# EMS-ESP8266-12.net
KiCad netlist of a schematic drawn in EAGLE
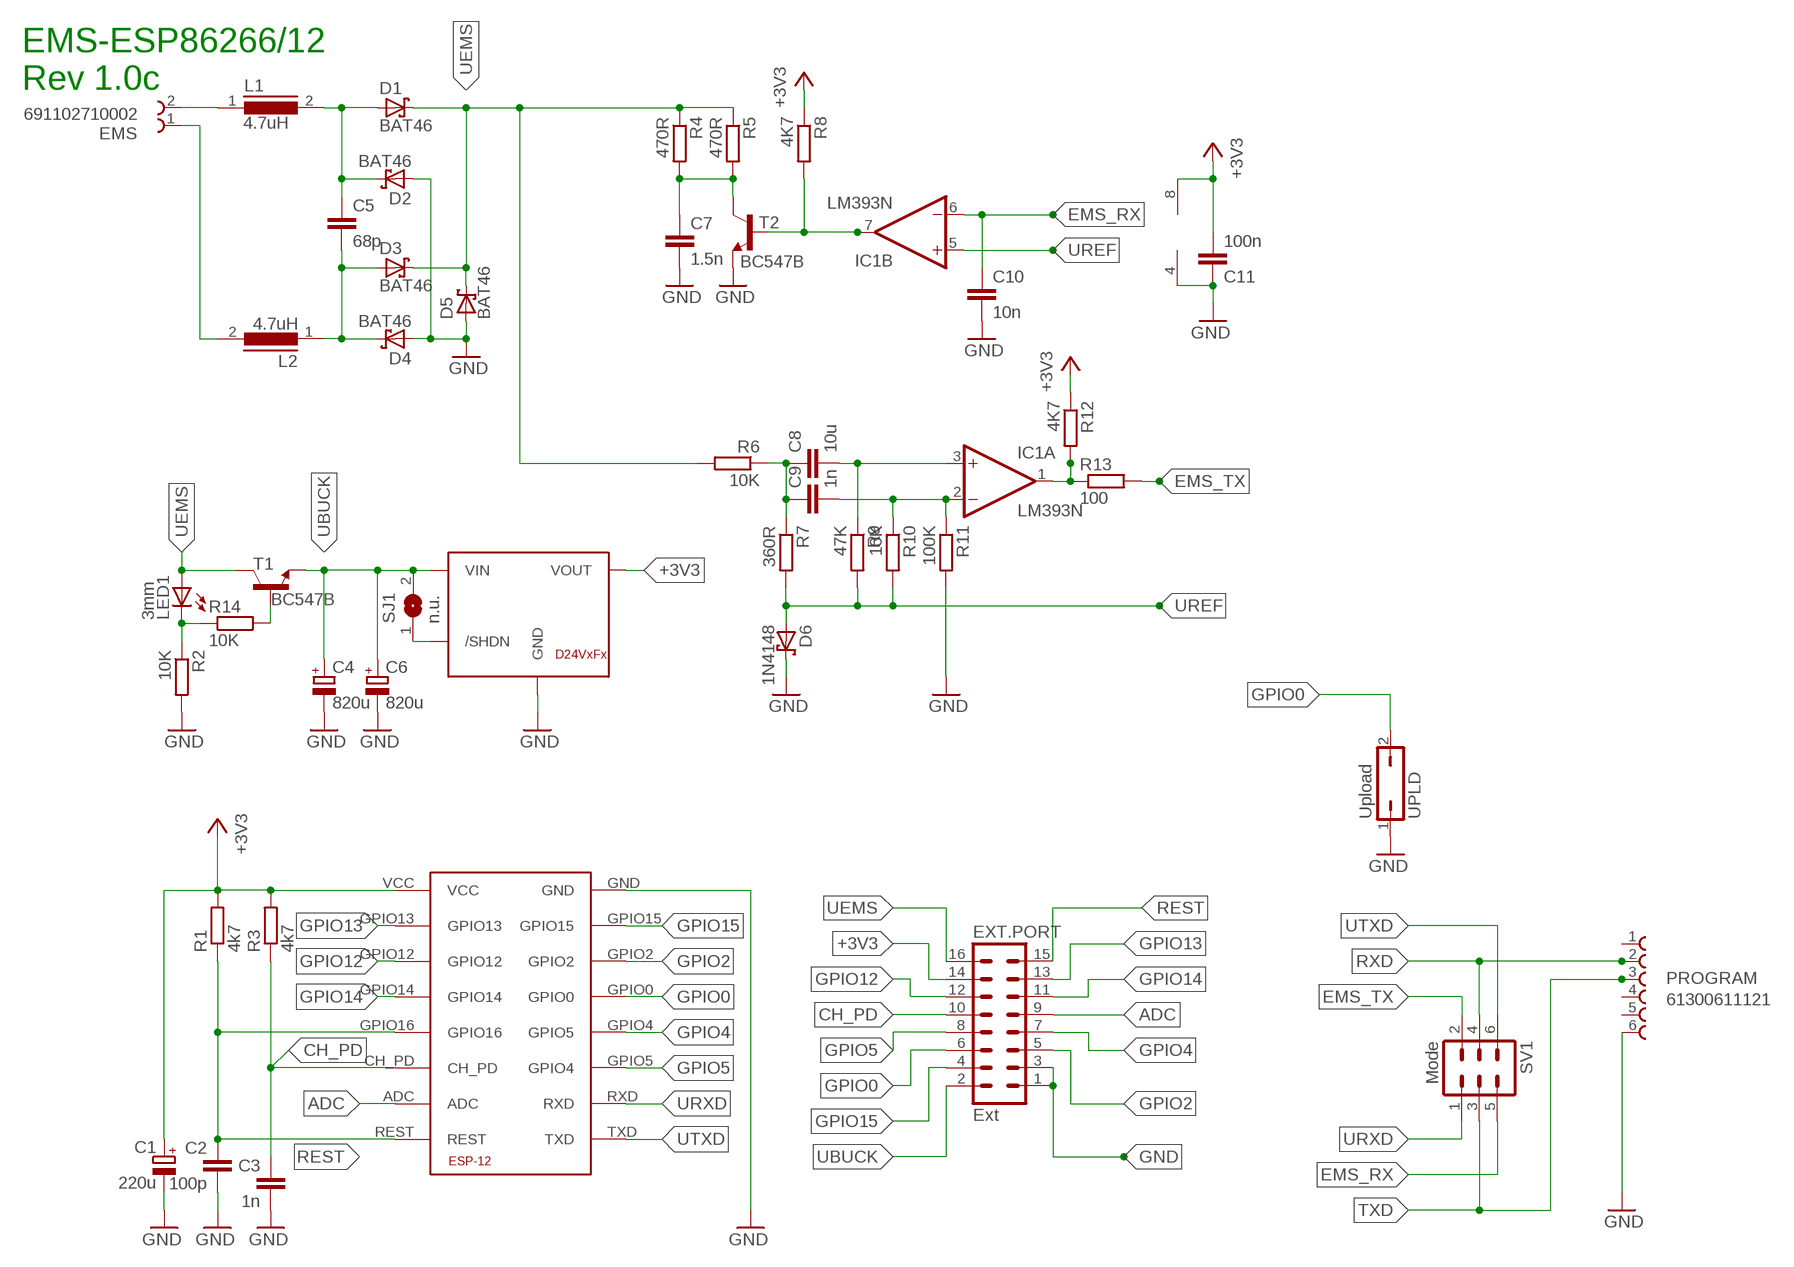
[diagram p0: schematic, sheet 1]

(export (version "E")
  (design (tool "Eeschema 10.0.6"))
  (components
    (comp (ref "C1")
      (value "220u")
      (footprint "eagle-import:UD-6,3X5,8_NICHICON")
      (libsource (lib "eagle-import") (part "CPOL-EUUD-6,3X8,8"))
    )
    (comp (ref "C2")
      (value "100p")
      (footprint "eagle-import:C2.5-2")
      (libsource (lib "eagle-import") (part "C2.5/2"))
    )
    (comp (ref "C3")
      (value "1n")
      (footprint "eagle-import:C2.5-2")
      (libsource (lib "eagle-import") (part "C2.5/2"))
    )
    (comp (ref "C4")
      (value "820u")
      (footprint "eagle-import:UD-10X10_NICHICON")
      (libsource (lib "eagle-import") (part "CPOL-EUUD-10X10"))
    )
    (comp (ref "C5")
      (value "68p")
      (footprint "eagle-import:C025-050X050")
      (libsource (lib "eagle-import") (part "C-EU025-050X050"))
    )
    (comp (ref "C6")
      (value "820u")
      (footprint "eagle-import:UD-10X10_NICHICON")
      (libsource (lib "eagle-import") (part "CPOL-EUUD-10X10"))
    )
    (comp (ref "C7")
      (value "1.5n")
      (footprint "eagle-import:C2.5-2")
      (libsource (lib "eagle-import") (part "C2.5/2"))
    )
    (comp (ref "C8")
      (value "10u")
      (footprint "eagle-import:C5B11")
      (libsource (lib "eagle-import") (part "C5/11"))
    )
    (comp (ref "C9")
      (value "1n")
      (footprint "eagle-import:C2.5-2")
      (libsource (lib "eagle-import") (part "C2.5/2"))
    )
    (comp (ref "C10")
      (value "10n")
      (footprint "eagle-import:C2.5-2")
      (libsource (lib "eagle-import") (part "C2.5/2"))
    )
    (comp (ref "C11")
      (value "100n")
      (footprint "eagle-import:C2.5-2")
      (libsource (lib "eagle-import") (part "C2.5/2"))
    )
    (comp (ref "D1")
      (value "BAT46")
      (footprint "eagle-import:DO35-7")
      (libsource (lib "eagle-import") (part "SCHOTTKY-DIODEDO35-7"))
    )
    (comp (ref "D2")
      (value "BAT46")
      (footprint "eagle-import:DO35-7")
      (libsource (lib "eagle-import") (part "SCHOTTKY-DIODEDO35-7"))
    )
    (comp (ref "D3")
      (value "BAT46")
      (footprint "eagle-import:DO35-7")
      (libsource (lib "eagle-import") (part "SCHOTTKY-DIODEDO35-7"))
    )
    (comp (ref "D4")
      (value "BAT46")
      (footprint "eagle-import:DO35-7")
      (libsource (lib "eagle-import") (part "SCHOTTKY-DIODEDO35-7"))
    )
    (comp (ref "D5")
      (value "BAT46")
      (footprint "eagle-import:DO35-7")
      (libsource (lib "eagle-import") (part "SCHOTTKY-DIODEDO35-7"))
    )
    (comp (ref "D6")
      (value "1N4148")
      (footprint "eagle-import:DO35-7")
      (libsource (lib "eagle-import") (part "SCHOTTKY-DIODEDO35-7"))
    )
    (comp (ref "EMS")
      (value "691102710002")
      (footprint "eagle-import:691102710002")
      (libsource (lib "eagle-import") (part "691102710002"))
    )
    (comp (ref "ESP1")
      (value "ESP-12ESP-12")
      (footprint "eagle-import:ESP-12")
      (libsource (lib "eagle-import") (part "ESP-12ESP-12"))
    )
    (comp (ref "EXT.PORT")
      (value "Ext")
      (footprint "eagle-import:MA08-2")
      (libsource (lib "eagle-import") (part "MA08-2"))
    )
    (comp (ref "IC1")
      (value "LM393N")
      (footprint "eagle-import:DIL08")
      (fields (field (name "REICHELT") "LM 393 DIP"))
      (libsource (lib "eagle-import") (part "LM393N"))
    )
    (comp (ref "L1")
      (value "4.7uH")
      (footprint "eagle-import:MICC12")
      (libsource (lib "eagle-import") (part "MICC12"))
    )
    (comp (ref "L2")
      (value "4.7uH")
      (footprint "eagle-import:MICC12")
      (libsource (lib "eagle-import") (part "MICC12"))
    )
    (comp (ref "LED1")
      (value "3mm")
      (footprint "eagle-import:LED3MM")
      (libsource (lib "eagle-import") (part "LED3MM"))
    )
    (comp (ref "MOD1")
      (value "D24V3F3")
      (footprint "eagle-import:D24VXFX")
      (libsource (lib "eagle-import") (part "D24VXFX"))
    )
    (comp (ref "PROGRAM")
      (value "61300611121")
      (footprint "eagle-import:61300611121")
      (libsource (lib "eagle-import") (part "61300611121"))
    )
    (comp (ref "R1")
      (value "4k7")
      (footprint "eagle-import:0204_7")
      (libsource (lib "eagle-import") (part "R-EU_0204/7"))
    )
    (comp (ref "R2")
      (value "10K")
      (footprint "eagle-import:0204_7")
      (libsource (lib "eagle-import") (part "R-EU_0204/7"))
    )
    (comp (ref "R3")
      (value "4k7")
      (footprint "eagle-import:0204_7")
      (libsource (lib "eagle-import") (part "R-EU_0204/7"))
    )
    (comp (ref "R4")
      (value "470R")
      (footprint "eagle-import:0204_7")
      (libsource (lib "eagle-import") (part "R-EU_0204/7"))
    )
    (comp (ref "R5")
      (value "470R")
      (footprint "eagle-import:0204_7")
      (libsource (lib "eagle-import") (part "R-EU_0204/7"))
    )
    (comp (ref "R6")
      (value "10K")
      (footprint "eagle-import:0204_7")
      (libsource (lib "eagle-import") (part "R-EU_0204/7"))
    )
    (comp (ref "R7")
      (value "360R")
      (footprint "eagle-import:0204_7")
      (libsource (lib "eagle-import") (part "R-EU_0204/7"))
    )
    (comp (ref "R8")
      (value "4K7")
      (footprint "eagle-import:0204_7")
      (libsource (lib "eagle-import") (part "R-EU_0204/7"))
    )
    (comp (ref "R9")
      (value "47K")
      (footprint "eagle-import:0204_7")
      (libsource (lib "eagle-import") (part "R-EU_0204/7"))
    )
    (comp (ref "R10")
      (value "10K")
      (footprint "eagle-import:0204_7")
      (libsource (lib "eagle-import") (part "R-EU_0204/7"))
    )
    (comp (ref "R11")
      (value "100K")
      (footprint "eagle-import:0204_7")
      (libsource (lib "eagle-import") (part "R-EU_0204/7"))
    )
    (comp (ref "R12")
      (value "4K7")
      (footprint "eagle-import:0204_7")
      (libsource (lib "eagle-import") (part "R-EU_0204/7"))
    )
    (comp (ref "R13")
      (value "100")
      (footprint "eagle-import:0204_7")
      (libsource (lib "eagle-import") (part "R-EU_0204/7"))
    )
    (comp (ref "R14")
      (value "10K")
      (footprint "eagle-import:0204_7")
      (libsource (lib "eagle-import") (part "R-EU_0204/7"))
    )
    (comp (ref "SJ1")
      (value "n.u.")
      (footprint "eagle-import:SJ")
      (libsource (lib "eagle-import") (part "SJ"))
    )
    (comp (ref "SV1")
      (value "Mode")
      (footprint "eagle-import:MA03-2")
      (libsource (lib "eagle-import") (part "MA03-2"))
    )
    (comp (ref "T1")
      (value "BC547B")
      (footprint "eagle-import:TO92")
      (libsource (lib "eagle-import") (part "-NPN-TO92"))
    )
    (comp (ref "T2")
      (value "BC547B")
      (footprint "eagle-import:TO92")
      (libsource (lib "eagle-import") (part "-NPN-TO92"))
    )
    (comp (ref "UPLD")
      (value "Upload")
      (footprint "eagle-import:JP1")
      (libsource (lib "eagle-import") (part "JP1Q"))
    )
  )
  (nets
    (net (code "1") (name "+3V3") (class "Default")
      (node (ref "C1") (pin "+") (pinfunction "+_+") (pintype "passive"))
      (node (ref "C11") (pin "2") (pinfunction "2_2") (pintype "passive"))
      (node (ref "ESP1") (pin "VCC") (pinfunction "VCC_VCC") (pintype "bidirectional"))
      (node (ref "EXT.PORT") (pin "14") (pinfunction "14_14") (pintype "passive"))
      (node (ref "IC1") (pin "8") (pinfunction "V+_8") (pintype "power_in"))
      (node (ref "MOD1") (pin "VOUT") (pinfunction "VOUT_VOUT") (pintype "power_in"))
      (node (ref "R1") (pin "2") (pinfunction "2_2") (pintype "passive"))
      (node (ref "R12") (pin "1") (pinfunction "1_1") (pintype "passive"))
      (node (ref "R3") (pin "2") (pinfunction "2_2") (pintype "passive"))
      (node (ref "R8") (pin "1") (pinfunction "1_1") (pintype "passive"))
    )
    (net (code "2") (name "ADC") (class "Default")
      (node (ref "ESP1") (pin "ADC") (pinfunction "ADC_ADC") (pintype "bidirectional"))
      (node (ref "EXT.PORT") (pin "9") (pinfunction "9_9") (pintype "passive"))
    )
    (net (code "3") (name "CH_PD") (class "Default")
      (node (ref "C3") (pin "1") (pinfunction "1_1") (pintype "passive"))
      (node (ref "ESP1") (pin "CH_PD") (pinfunction "CH_PD_CH_PD") (pintype "bidirectional"))
      (node (ref "EXT.PORT") (pin "10") (pinfunction "10_10") (pintype "passive"))
      (node (ref "R3") (pin "1") (pinfunction "1_1") (pintype "passive"))
    )
    (net (code "4") (name "EMS_RX") (class "Default")
      (node (ref "C10") (pin "1") (pinfunction "1_1") (pintype "passive"))
      (node (ref "IC1") (pin "6") (pinfunction "-IN_6") (pintype "input"))
      (node (ref "SV1") (pin "5") (pinfunction "5_5") (pintype "passive"))
    )
    (net (code "5") (name "EMS_TX") (class "Default")
      (node (ref "R13") (pin "2") (pinfunction "2_2") (pintype "passive"))
      (node (ref "SV1") (pin "2") (pinfunction "2_2") (pintype "passive"))
    )
    (net (code "6") (name "GND") (class "Default")
      (node (ref "C1") (pin "-") (pinfunction "-_-") (pintype "passive"))
      (node (ref "C10") (pin "2") (pinfunction "2_2") (pintype "passive"))
      (node (ref "C11") (pin "1") (pinfunction "1_1") (pintype "passive"))
      (node (ref "C2") (pin "2") (pinfunction "2_2") (pintype "passive"))
      (node (ref "C3") (pin "2") (pinfunction "2_2") (pintype "passive"))
      (node (ref "C4") (pin "-") (pinfunction "-_-") (pintype "passive"))
      (node (ref "C6") (pin "-") (pinfunction "-_-") (pintype "passive"))
      (node (ref "C7") (pin "2") (pinfunction "2_2") (pintype "passive"))
      (node (ref "D2") (pin "A") (pinfunction "A_A") (pintype "passive"))
      (node (ref "D4") (pin "A") (pinfunction "A_A") (pintype "passive"))
      (node (ref "D5") (pin "A") (pinfunction "A_A") (pintype "passive"))
      (node (ref "D6") (pin "C") (pinfunction "C_C") (pintype "passive"))
      (node (ref "ESP1") (pin "GND") (pinfunction "GND_GND") (pintype "bidirectional"))
      (node (ref "EXT.PORT") (pin "1") (pinfunction "1_1") (pintype "passive"))
      (node (ref "EXT.PORT") (pin "3") (pinfunction "3_3") (pintype "passive"))
      (node (ref "IC1") (pin "4") (pinfunction "V-_4") (pintype "power_in"))
      (node (ref "MOD1") (pin "GND") (pinfunction "GND_GND") (pintype "power_in"))
      (node (ref "PROGRAM") (pin "6") (pinfunction "6_6") (pintype "passive"))
      (node (ref "R11") (pin "2") (pinfunction "2_2") (pintype "passive"))
      (node (ref "R2") (pin "2") (pinfunction "2_2") (pintype "passive"))
      (node (ref "T2") (pin "1") (pinfunction "E_1") (pintype "passive"))
      (node (ref "UPLD") (pin "1") (pinfunction "1_1") (pintype "passive"))
    )
    (net (code "7") (name "GPIO0") (class "Default")
      (node (ref "ESP1") (pin "GPIO0") (pinfunction "GPIO0_GPIO0") (pintype "bidirectional"))
      (node (ref "EXT.PORT") (pin "6") (pinfunction "6_6") (pintype "passive"))
      (node (ref "UPLD") (pin "2") (pinfunction "2_2") (pintype "passive"))
    )
    (net (code "8") (name "GPIO2") (class "Default")
      (node (ref "ESP1") (pin "GPIO2") (pinfunction "GPIO2_GPIO2") (pintype "bidirectional"))
      (node (ref "EXT.PORT") (pin "5") (pinfunction "5_5") (pintype "passive"))
    )
    (net (code "9") (name "GPIO4") (class "Default")
      (node (ref "ESP1") (pin "GPIO4") (pinfunction "GPIO5_GPIO4") (pintype "bidirectional"))
      (node (ref "EXT.PORT") (pin "7") (pinfunction "7_7") (pintype "passive"))
    )
    (net (code "10") (name "GPIO5") (class "Default")
      (node (ref "ESP1") (pin "GPIO5") (pinfunction "GPIO4_GPIO5") (pintype "bidirectional"))
      (node (ref "EXT.PORT") (pin "8") (pinfunction "8_8") (pintype "passive"))
    )
    (net (code "11") (name "GPIO12") (class "Default")
      (node (ref "ESP1") (pin "GPIO12") (pinfunction "GPIO12_GPIO12") (pintype "bidirectional"))
      (node (ref "EXT.PORT") (pin "12") (pinfunction "12_12") (pintype "passive"))
    )
    (net (code "12") (name "GPIO13") (class "Default")
      (node (ref "ESP1") (pin "GPIO13") (pinfunction "GPIO13_GPIO13") (pintype "bidirectional"))
      (node (ref "EXT.PORT") (pin "13") (pinfunction "13_13") (pintype "passive"))
    )
    (net (code "13") (name "GPIO14") (class "Default")
      (node (ref "ESP1") (pin "GPIO14") (pinfunction "GPIO14_GPIO14") (pintype "bidirectional"))
      (node (ref "EXT.PORT") (pin "11") (pinfunction "11_11") (pintype "passive"))
    )
    (net (code "14") (name "GPIO15") (class "Default")
      (node (ref "ESP1") (pin "GPIO15") (pinfunction "GPIO15_GPIO15") (pintype "bidirectional"))
      (node (ref "EXT.PORT") (pin "4") (pinfunction "4_4") (pintype "passive"))
    )
    (net (code "15") (name "Net-(C5-Pad1)") (class "Default")
      (node (ref "C5") (pin "1") (pinfunction "1_1") (pintype "passive"))
      (node (ref "D1") (pin "A") (pinfunction "A_A") (pintype "passive"))
      (node (ref "D2") (pin "C") (pinfunction "C_C") (pintype "passive"))
      (node (ref "L1") (pin "2") (pinfunction "2_2") (pintype "passive"))
    )
    (net (code "16") (name "Net-(C5-Pad2)") (class "Default")
      (node (ref "C5") (pin "2") (pinfunction "2_2") (pintype "passive"))
      (node (ref "D3") (pin "A") (pinfunction "A_A") (pintype "passive"))
      (node (ref "D4") (pin "C") (pinfunction "C_C") (pintype "passive"))
      (node (ref "L2") (pin "1") (pinfunction "1_1") (pintype "passive"))
    )
    (net (code "17") (name "Net-(C8-Pad1)") (class "Default")
      (node (ref "C8") (pin "1") (pinfunction "1_1") (pintype "passive"))
      (node (ref "C9") (pin "1") (pinfunction "1_1") (pintype "passive"))
      (node (ref "R6") (pin "1") (pinfunction "1_1") (pintype "passive"))
      (node (ref "R7") (pin "1") (pinfunction "1_1") (pintype "passive"))
    )
    (net (code "18") (name "Net-(EMS-Pad1)") (class "Default")
      (node (ref "EMS") (pin "1") (pinfunction "1_1") (pintype "passive"))
      (node (ref "L2") (pin "2") (pinfunction "2_2") (pintype "passive"))
    )
    (net (code "19") (name "Net-(EMS-Pad2)") (class "Default")
      (node (ref "EMS") (pin "2") (pinfunction "2_2") (pintype "passive"))
      (node (ref "L1") (pin "1") (pinfunction "1_1") (pintype "passive"))
    )
    (net (code "20") (name "Net-(IC1A-+IN)") (class "Default")
      (node (ref "C8") (pin "2") (pinfunction "2_2") (pintype "passive"))
      (node (ref "IC1") (pin "3") (pinfunction "+IN_3") (pintype "input"))
      (node (ref "R9") (pin "1") (pinfunction "1_1") (pintype "passive"))
    )
    (net (code "21") (name "Net-(IC1A--IN)") (class "Default")
      (node (ref "C9") (pin "2") (pinfunction "2_2") (pintype "passive"))
      (node (ref "IC1") (pin "2") (pinfunction "-IN_2") (pintype "input"))
      (node (ref "R10") (pin "1") (pinfunction "1_1") (pintype "passive"))
      (node (ref "R11") (pin "1") (pinfunction "1_1") (pintype "passive"))
    )
    (net (code "22") (name "Net-(IC1A-OUT)") (class "Default")
      (node (ref "IC1") (pin "1") (pinfunction "OUT_1") (pintype "output"))
      (node (ref "R12") (pin "2") (pinfunction "2_2") (pintype "passive"))
      (node (ref "R13") (pin "1") (pinfunction "1_1") (pintype "passive"))
    )
    (net (code "23") (name "Net-(IC1B-OUT)") (class "Default")
      (node (ref "IC1") (pin "7") (pinfunction "OUT_7") (pintype "output"))
      (node (ref "R8") (pin "2") (pinfunction "2_2") (pintype "passive"))
      (node (ref "T2") (pin "2") (pinfunction "B_2") (pintype "passive"))
    )
    (net (code "24") (name "Net-(LED1-C)") (class "Default")
      (node (ref "LED1") (pin "K") (pinfunction "C_K") (pintype "passive"))
      (node (ref "R14") (pin "1") (pinfunction "1_1") (pintype "passive"))
      (node (ref "R2") (pin "1") (pinfunction "1_1") (pintype "passive"))
    )
    (net (code "25") (name "Net-(MOD1-Pad{slash}SHDN)") (class "Default")
      (node (ref "MOD1") (pin "/SHDN") (pinfunction "/SHDN_/SHDN") (pintype "input"))
      (node (ref "SJ1") (pin "1") (pinfunction "1_1") (pintype "passive"))
    )
    (net (code "26") (name "Net-(T1-B)") (class "Default")
      (node (ref "R14") (pin "2") (pinfunction "2_2") (pintype "passive"))
      (node (ref "T1") (pin "2") (pinfunction "B_2") (pintype "passive"))
    )
    (net (code "27") (name "Net-(T2-C)") (class "Default")
      (node (ref "C7") (pin "1") (pinfunction "1_1") (pintype "passive"))
      (node (ref "R4") (pin "2") (pinfunction "2_2") (pintype "passive"))
      (node (ref "R5") (pin "2") (pinfunction "2_2") (pintype "passive"))
      (node (ref "T2") (pin "3") (pinfunction "C_3") (pintype "passive"))
    )
    (net (code "28") (name "REST") (class "Default")
      (node (ref "C2") (pin "1") (pinfunction "1_1") (pintype "passive"))
      (node (ref "ESP1") (pin "GPIO16") (pinfunction "GPIO16_GPIO16") (pintype "bidirectional"))
      (node (ref "ESP1") (pin "REST") (pinfunction "REST_REST") (pintype "bidirectional"))
      (node (ref "EXT.PORT") (pin "15") (pinfunction "15_15") (pintype "passive"))
      (node (ref "R1") (pin "1") (pinfunction "1_1") (pintype "passive"))
    )
    (net (code "29") (name "RXD") (class "Default")
      (node (ref "PROGRAM") (pin "2") (pinfunction "2_2") (pintype "passive"))
      (node (ref "SV1") (pin "4") (pinfunction "4_4") (pintype "passive"))
    )
    (net (code "30") (name "TXD") (class "Default")
      (node (ref "PROGRAM") (pin "3") (pinfunction "3_3") (pintype "passive"))
      (node (ref "SV1") (pin "3") (pinfunction "3_3") (pintype "passive"))
    )
    (net (code "31") (name "UBUCK") (class "Default")
      (node (ref "C4") (pin "+") (pinfunction "+_+") (pintype "passive"))
      (node (ref "C6") (pin "+") (pinfunction "+_+") (pintype "passive"))
      (node (ref "EXT.PORT") (pin "2") (pinfunction "2_2") (pintype "passive"))
      (node (ref "MOD1") (pin "VIN") (pinfunction "VIN_VIN") (pintype "power_in"))
      (node (ref "SJ1") (pin "2") (pinfunction "2_2") (pintype "passive"))
      (node (ref "T1") (pin "1") (pinfunction "E_1") (pintype "passive"))
    )
    (net (code "32") (name "UEMS") (class "Default")
      (node (ref "D1") (pin "C") (pinfunction "C_C") (pintype "passive"))
      (node (ref "D3") (pin "C") (pinfunction "C_C") (pintype "passive"))
      (node (ref "D5") (pin "C") (pinfunction "C_C") (pintype "passive"))
      (node (ref "EXT.PORT") (pin "16") (pinfunction "16_16") (pintype "passive"))
      (node (ref "LED1") (pin "A") (pinfunction "A_A") (pintype "passive"))
      (node (ref "R4") (pin "1") (pinfunction "1_1") (pintype "passive"))
      (node (ref "R5") (pin "1") (pinfunction "1_1") (pintype "passive"))
      (node (ref "R6") (pin "2") (pinfunction "2_2") (pintype "passive"))
      (node (ref "T1") (pin "3") (pinfunction "C_3") (pintype "passive"))
    )
    (net (code "33") (name "UREF") (class "Default")
      (node (ref "D6") (pin "A") (pinfunction "A_A") (pintype "passive"))
      (node (ref "IC1") (pin "5") (pinfunction "+IN_5") (pintype "input"))
      (node (ref "R10") (pin "2") (pinfunction "2_2") (pintype "passive"))
      (node (ref "R7") (pin "2") (pinfunction "2_2") (pintype "passive"))
      (node (ref "R9") (pin "2") (pinfunction "2_2") (pintype "passive"))
    )
    (net (code "34") (name "URXD") (class "Default")
      (node (ref "ESP1") (pin "RXD") (pinfunction "RXD_RXD") (pintype "bidirectional"))
      (node (ref "SV1") (pin "1") (pinfunction "1_1") (pintype "passive"))
    )
    (net (code "35") (name "UTXD") (class "Default")
      (node (ref "ESP1") (pin "TXD") (pinfunction "TXD_TXD") (pintype "bidirectional"))
      (node (ref "SV1") (pin "6") (pinfunction "6_6") (pintype "passive"))
    )
    (net (code "36") (name "unconnected-(PROGRAM-Pad1)") (class "Default")
      (node (ref "PROGRAM") (pin "1") (pinfunction "1_1") (pintype "passive"))
    )
    (net (code "37") (name "unconnected-(PROGRAM-Pad4)") (class "Default")
      (node (ref "PROGRAM") (pin "4") (pinfunction "4_4") (pintype "passive"))
    )
    (net (code "38") (name "unconnected-(PROGRAM-Pad5)") (class "Default")
      (node (ref "PROGRAM") (pin "5") (pinfunction "5_5") (pintype "passive"))
    )
  )
)
